# Sheet1.net
KiCad netlist of a schematic drawn in Altium Designer
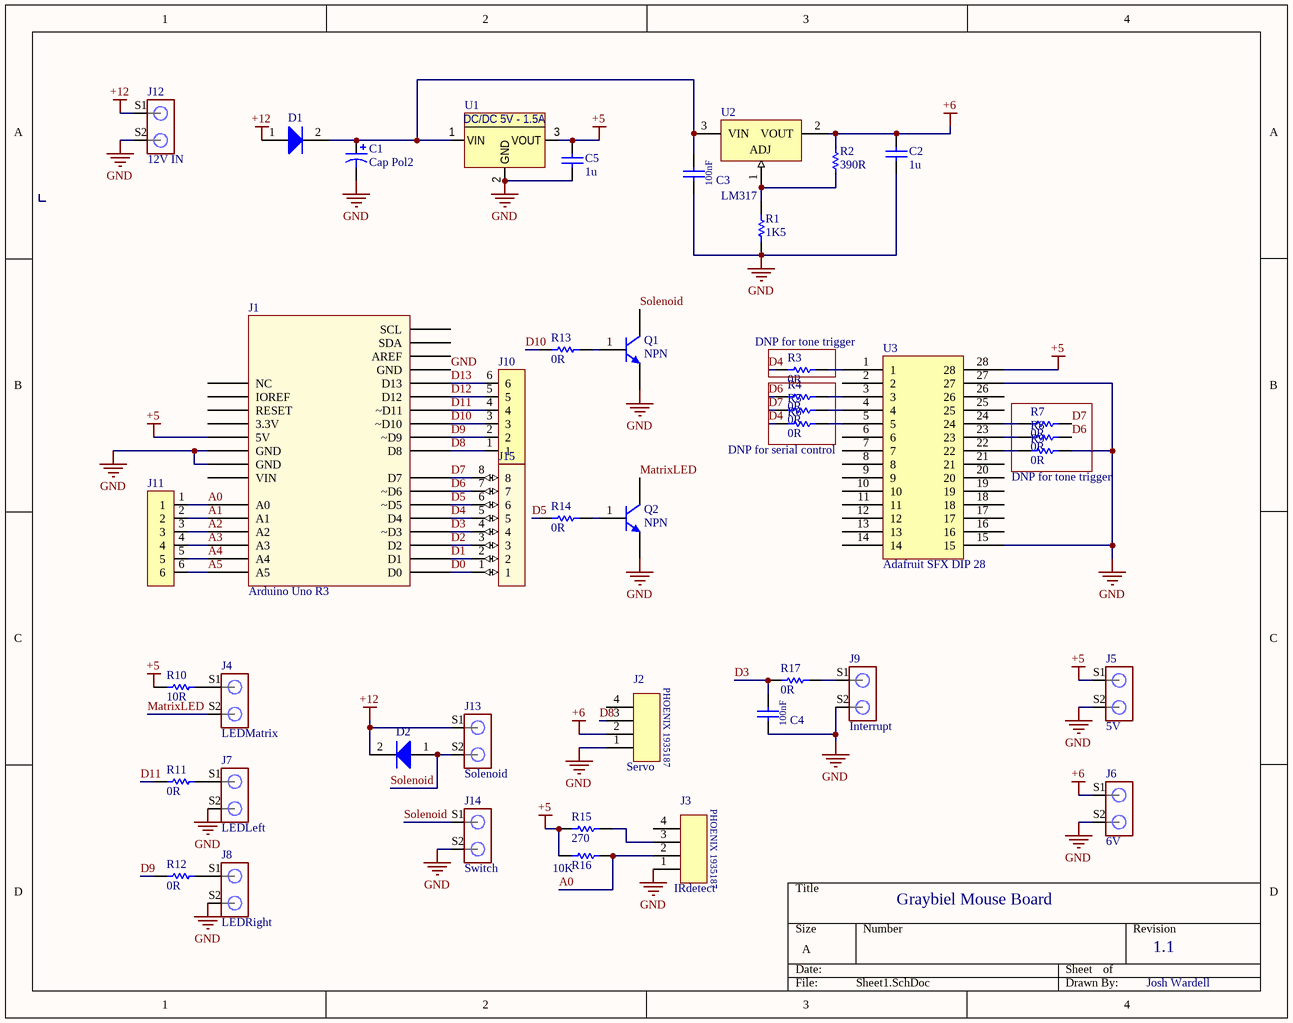
[diagram p0: Sheet1.SchDoc]

(export (version "E")
  (design (tool "Eeschema 10.0.6"))
  (components
    (comp (ref "C1")
      (value "Cap Pol2")
      (footprint "PCB-xqaiwfy5uu00k2ym2klb-1")
      (description "Capacitor; Alum Electrolytic; Cap 100 uF; Tol 20%; Vol-Rtg 25 VDC; Radial; 8x11.5; Bulk")
      (fields (field (name "MANUFACTURER PART NUMBER") "ECE-A1EN101U"))
      (libsource (lib "CommunityVault") (part "SYM-07bcccec45f2d87b-1"))
    )
    (comp (ref "C2")
      (value "1u")
      (footprint "CAPC2013X135X45ML10T25")
      (description "CAP CER 1UF 16V 10% X7R 0805")
      (libsource (lib "CommunityVault") (part "CAP-2"))
    )
    (comp (ref "C3")
      (value "SYM-3c98f6df3913e35f-6")
      (footprint "PCB-ukzk5524dky3o1p8ks6j-1")
      (description "Capacitor; Ceramic; Cap 0.1 uF; Tol 10%; Vol-Rtg 50 VDC; SMT; 0805; X7R; Cut Tape")
      (fields (field (name "MANUFACTURER PART NUMBER") "08055C104KAT2A"))
      (libsource (lib "CommunityVault") (part "SYM-3c98f6df3913e35f-6"))
    )
    (comp (ref "C4")
      (value "SYM-3c98f6df3913e35f-6")
      (footprint "PCB-ukzk5524dky3o1p8ks6j-1")
      (description "Capacitor; Ceramic; Cap 0.1 uF; Tol 10%; Vol-Rtg 50 VDC; SMT; 0805; X7R; Cut Tape")
      (fields (field (name "MANUFACTURER PART NUMBER") "08055C104KAT2A"))
      (libsource (lib "CommunityVault") (part "CMP-3c98f6df3913e35f-15"))
    )
    (comp (ref "C5")
      (value "1u")
      (footprint "CAPC2013X135X45ML10T25")
      (description "CAP CER 1UF 16V 10% X7R 0805")
      (libsource (lib "CommunityVault") (part "CAP-2"))
    )
    (comp (ref "D1")
      (value "SYM-5df394efdd628234-1")
      (footprint "PCB-b6kvxtdabtic7bh9bv58-1")
      (description "Rectifier diode [Diotec] 1N4004 Rectifier diode")
      (libsource (lib "CommunityVault") (part "CMP-5df394efdd628234-2"))
    )
    (comp (ref "D2")
      (value "SYM-5df394efdd628234-1")
      (footprint "PCB-b6kvxtdabtic7bh9bv58-1")
      (description "Rectifier diode [Diotec] 1N4004 Rectifier diode")
      (libsource (lib "CommunityVault") (part "CMP-5df394efdd628234-2"))
    )
    (comp (ref "J1")
      (value "Arduino Uno R3")
      (footprint "PCB-5e3n8s0ey5jqr2f9nncc-1")
      (description "Microcontroller board, Uno [Arduino] A000066 Microcontroller board, Uno 7640152110092")
      (fields (field (name "MANUFACTURER PART NUMBER") "A000066"))
      (libsource (lib "CommunityVault") (part "CMP-1073962-46"))
    )
    (comp (ref "J2")
      (value "Servo")
      (footprint "PCB-v9l72avc46uddy7fpuqf-1")
      (description "Screw terminal 2.50 mm² Number of pins 4 PT 1, 5/ 4-5, 0-H Phoenix Contact Green 1 pc(s)")
      (libsource (lib "CommunityVault") (part "CMP-f0b139bb75412f76-5"))
    )
    (comp (ref "J3")
      (value "IRdetect")
      (footprint "PCB-v9l72avc46uddy7fpuqf-1")
      (description "Screw terminal 2.50 mm² Number of pins 4 PT 1, 5/ 4-5, 0-H Phoenix Contact Green 1 pc(s)")
      (libsource (lib "CommunityVault") (part "CMP-f0b139bb75412f76-5"))
    )
    (comp (ref "J4")
      (value "LEDMatrix")
      (footprint "PCB-723450-1")
      (description "TERM BLOCK HEADER 2POS 5MM BLACK")
      (libsource (lib "CommunityVault") (part "CMP-723450-4"))
    )
    (comp (ref "J5")
      (value "5V")
      (footprint "PCB-723450-1")
      (description "TERM BLOCK HEADER 2POS 5MM BLACK")
      (libsource (lib "CommunityVault") (part "CMP-723450-4"))
    )
    (comp (ref "J6")
      (value "6V")
      (footprint "PCB-723450-1")
      (description "TERM BLOCK HEADER 2POS 5MM BLACK")
      (libsource (lib "CommunityVault") (part "CMP-723450-4"))
    )
    (comp (ref "J7")
      (value "LEDLeft")
      (footprint "PCB-723450-1")
      (description "TERM BLOCK HEADER 2POS 5MM BLACK")
      (libsource (lib "CommunityVault") (part "SYM-723450-1"))
    )
    (comp (ref "J8")
      (value "LEDRight")
      (footprint "PCB-723450-1")
      (description "TERM BLOCK HEADER 2POS 5MM BLACK")
      (libsource (lib "CommunityVault") (part "SYM-723450-1"))
    )
    (comp (ref "J9")
      (value "Interrupt")
      (footprint "PCB-723450-1")
      (description "TERM BLOCK HEADER 2POS 5MM BLACK")
      (libsource (lib "CommunityVault") (part "SYM-723450-1"))
    )
    (comp (ref "J10")
      (value "TE Connectivity / AMP 3-644456-5")
      (footprint "PCB-oudem42uhcimrbfznktg-1")
      (description "MTA-100 Series 6 Position 2.54 mm Pitch Single Row Tin Plated Header")
      (libsource (lib "CommunityVault") (part "CMP-7ab1b1e1ad8ca576-9"))
    )
    (comp (ref "J11")
      (value "TE Connectivity / AMP 3-644456-5")
      (footprint "PCB-oudem42uhcimrbfznktg-1")
      (description "MTA-100 Series 6 Position 2.54 mm Pitch Single Row Tin Plated Header")
      (libsource (lib "") (part "CMP-7ab1b1e1ad8ca576-9_1"))
    )
    (comp (ref "J12")
      (value "12V IN")
      (footprint "PCB-723450-1")
      (description "TERM BLOCK HEADER 2POS 5MM BLACK")
      (libsource (lib "CommunityVault") (part "CMP-723450-4"))
    )
    (comp (ref "J13")
      (value "Solenoid")
      (footprint "PCB-723450-1")
      (description "TERM BLOCK HEADER 2POS 5MM BLACK")
      (libsource (lib "CommunityVault") (part "SYM-723450-1"))
    )
    (comp (ref "J14")
      (value "Switch")
      (footprint "PCB-723450-1")
      (description "TERM BLOCK HEADER 2POS 5MM BLACK")
      (libsource (lib "CommunityVault") (part "SYM-723450-1"))
    )
    (comp (ref "J15")
      (value "Samtec TSW-108-07-L-S")
      (footprint "PCB-o70tqi8axh3k6d5wp5n8-1")
      (description "HEADER, 2.54MM, THT VERT, 8POS; Series: TSW; Pitch Spacing: 2.54mm; No. of Rows: 1;")
      (fields (field (name "MANUFACTURER PART NUMBER") "TSW-108-07-L-S"))
      (libsource (lib "CommunityVault") (part "CMP-69fea0f06b37b639-1"))
    )
    (comp (ref "Q1")
      (value "NPN")
      (footprint "PCB-7rwmerlkdpdu5vtj8obn-1")
      (description "Trans Darlington NPN 60V 5A 2000mW Automotive 3-Pin(3+Tab) TO-220AB Bag")
      (fields (field (name "MANUFACTURER PART NUMBER") "TIP120"))
      (libsource (lib "CommunityVault") (part "CMP-3d84f48b638ce243-2"))
    )
    (comp (ref "Q2")
      (value "NPN")
      (footprint "PCB-7rwmerlkdpdu5vtj8obn-1")
      (description "Trans Darlington NPN 60V 5A 2000mW Automotive 3-Pin(3+Tab) TO-220AB Bag")
      (fields (field (name "MANUFACTURER PART NUMBER") "TIP120"))
      (libsource (lib "CommunityVault") (part "CMP-3d84f48b638ce243-2"))
    )
    (comp (ref "R1")
      (value "Res1")
      (footprint "PCB-lpea0est4zq6qerl2uei-1")
      (fields (field (name "RESISTANCE") "1K5") (field (name "MANUFACTURER PART NUMBER") "ERJ-6ENF3900V"))
      (libsource (lib "CommunityVault") (part "CMP-7c05b642f7a2a3c2-1"))
    )
    (comp (ref "R2")
      (value "Panasonic ERJ-6ENF1501V")
      (footprint "RESC2013X70X40ML20T20")
      (description "Thick Film Resistors 0805 1.5Kohms 1% Tol")
      (fields (field (name "RESISTANCE") "390R"))
      (libsource (lib "CommunityVault") (part "CMP-3652227-3"))
    )
    (comp (ref "R3")
      (value "0R")
      (footprint "RESC2013X65X35NL10T20")
      (description "Panasonic Resistor 0 Ohm 0805")
      (fields
        (field (name "MANUFACTURER PART NUMBER") "ERJ-6GEY0R00V")
        (field (name "MANUFACTURER") "Panasonic")
      )
      (libsource (lib "CommunityVault") (part "RES-2"))
    )
    (comp (ref "R4")
      (value "0R")
      (footprint "RESC2013X65X35NL10T20")
      (description "Panasonic Resistor 0 Ohm 0805")
      (fields
        (field (name "MANUFACTURER PART NUMBER") "ERJ-6GEY0R00V")
        (field (name "MANUFACTURER") "Panasonic")
      )
      (libsource (lib "CommunityVault") (part "RES-2"))
    )
    (comp (ref "R5")
      (value "0R")
      (footprint "RESC2013X65X35NL10T20")
      (description "Panasonic Resistor 0 Ohm 0805")
      (fields
        (field (name "MANUFACTURER PART NUMBER") "ERJ-6GEY0R00V")
        (field (name "MANUFACTURER") "Panasonic")
      )
      (libsource (lib "CommunityVault") (part "RES-2"))
    )
    (comp (ref "R6")
      (value "0R")
      (footprint "RESC2013X65X35NL10T20")
      (description "Panasonic Resistor 0 Ohm 0805")
      (fields
        (field (name "MANUFACTURER PART NUMBER") "ERJ-6GEY0R00V")
        (field (name "MANUFACTURER") "Panasonic")
      )
      (libsource (lib "CommunityVault") (part "RES-2"))
    )
    (comp (ref "R7")
      (value "0R")
      (footprint "RESC2013X65X35NL10T20")
      (description "Panasonic Resistor 0 Ohm 0805")
      (fields
        (field (name "MANUFACTURER PART NUMBER") "ERJ-6GEY0R00V")
        (field (name "MANUFACTURER") "Panasonic")
      )
      (libsource (lib "CommunityVault") (part "RES-2"))
    )
    (comp (ref "R8")
      (value "0R")
      (footprint "RESC2013X65X35NL10T20")
      (description "Panasonic Resistor 0 Ohm 0805")
      (fields
        (field (name "MANUFACTURER PART NUMBER") "ERJ-6GEY0R00V")
        (field (name "MANUFACTURER") "Panasonic")
      )
      (libsource (lib "CommunityVault") (part "RES-2"))
    )
    (comp (ref "R9")
      (value "0R")
      (footprint "RESC2013X65X35NL10T20")
      (description "Panasonic Resistor 0 Ohm 0805")
      (fields
        (field (name "MANUFACTURER PART NUMBER") "ERJ-6GEY0R00V")
        (field (name "MANUFACTURER") "Panasonic")
      )
      (libsource (lib "CommunityVault") (part "RES-2"))
    )
    (comp (ref "R10")
      (value "10R")
      (footprint "PCB-tug24or67yk1neb49pkx-1")
      (description "Surface Mount Chip Resistor, Thick Film, CRS Series, 10 ohm, 1 W, 5%, 400 V, 2010 [5025 Metric]")
      (fields (field (name "MANUFACTURER PART NUMBER") "CRS2010-JX-100ELF"))
      (libsource (lib "CommunityVault") (part "CMP-196dd32a6f1ac6aa-1"))
    )
    (comp (ref "R11")
      (value "0R")
      (footprint "RESC2013X65X35NL10T20")
      (description "Panasonic Resistor 0 Ohm 0805")
      (fields
        (field (name "MANUFACTURER PART NUMBER") "ERJ-6GEY0R00V")
        (field (name "MANUFACTURER") "Panasonic")
      )
      (libsource (lib "CommunityVault") (part "RES-2"))
    )
    (comp (ref "R12")
      (value "0R")
      (footprint "RESC2013X65X35NL10T20")
      (description "Panasonic Resistor 0 Ohm 0805")
      (fields
        (field (name "MANUFACTURER PART NUMBER") "ERJ-6GEY0R00V")
        (field (name "MANUFACTURER") "Panasonic")
      )
      (libsource (lib "CommunityVault") (part "RES-2"))
    )
    (comp (ref "R13")
      (value "0R")
      (footprint "RESC2013X65X35NL10T20")
      (description "Panasonic Resistor 0 Ohm 0805")
      (fields
        (field (name "MANUFACTURER PART NUMBER") "ERJ-6GEY0R00V")
        (field (name "MANUFACTURER") "Panasonic")
      )
      (libsource (lib "CommunityVault") (part "RES-2"))
    )
    (comp (ref "R14")
      (value "0R")
      (footprint "RESC2013X65X35NL10T20")
      (description "Panasonic Resistor 0 Ohm 0805")
      (fields
        (field (name "MANUFACTURER PART NUMBER") "ERJ-6GEY0R00V")
        (field (name "MANUFACTURER") "Panasonic")
      )
      (libsource (lib "CommunityVault") (part "RES-2"))
    )
    (comp (ref "R15")
      (value "270")
      (footprint "RESC2013X50X30ML20T20")
      (description "Thick film resistor")
      (libsource (lib "CommunityVault") (part "RES-2"))
    )
    (comp (ref "R16")
      (value "10K")
      (footprint "PCB-jmrvwrcl0dwqv7ke6mfz-1")
      (description "Res Thick Film 0805 10K Ohm 1% 0.125W(1/8W) ±100ppm/C Molded SMD Automotive Paper T/R")
      (libsource (lib "CommunityVault") (part "CMP-4716692-8"))
    )
    (comp (ref "R17")
      (value "0R")
      (footprint "RESC2013X65X35NL10T20")
      (description "Panasonic Resistor 0 Ohm 0805")
      (fields
        (field (name "MANUFACTURER PART NUMBER") "ERJ-6GEY0R00V")
        (field (name "MANUFACTURER") "Panasonic")
      )
      (libsource (lib "CommunityVault") (part "RES-2"))
    )
    (comp (ref "U1")
      (value "Murata OKI-78SR-5/1.5-W36H-C")
      (footprint "OKI-78SR-5/1.5-W36H-C")
      (description "DC/DC Converters 7.5W 24V 5Vout 1.5A Horizontal Mount")
      (libsource (lib "CommunityVault") (part "CMP-3191555-6"))
    )
    (comp (ref "U2")
      (value "LM317")
      (footprint "PCB-d58nmo5dooqatgqjfgwp-1")
      (libsource (lib "CommunityVault") (part "CMP-bbed72e7deae642a-4"))
    )
    (comp (ref "U3")
      (value "Adafruit SFX DIP 28")
      (footprint "PCB-bcfalq7aliu97ymsl87v-1")
      (description "Adafruit Audio FX Sound Board - WAV/OGG Trigger with 2MB Flash")
      (fields (field (name "MANUFACTURER") "Adafruit") (field (name "MANUFACTURER PART NUMBER") "2133"))
      (libsource (lib "CommunityVault") (part "CMP-4t4546zhglsm7c6ybtqr-1"))
    )
  )
  (nets
    (net (code "1") (name "+5") (class "Default")
      (node (ref "C5") (pin "2") (pinfunction "2_2") (pintype "passive"))
      (node (ref "J1") (pin "5V") (pinfunction "5V_5V") (pintype "passive"))
      (node (ref "J5") (pin "S1") (pinfunction "S1_S1") (pintype "passive"))
      (node (ref "R10") (pin "2") (pinfunction "2_2") (pintype "passive"))
      (node (ref "R15") (pin "1") (pinfunction "1_1") (pintype "passive"))
      (node (ref "R16") (pin "1") (pinfunction "1_1") (pintype "passive"))
      (node (ref "U1") (pin "3") (pinfunction "VOUT_3") (pintype "power_in"))
      (node (ref "U3") (pin "28") (pinfunction "28_28") (pintype "passive"))
    )
    (net (code "2") (name "+6") (class "Default")
      (node (ref "C2") (pin "2") (pinfunction "2_2") (pintype "passive"))
      (node (ref "J2") (pin "2") (pinfunction "2_2") (pintype "passive"))
      (node (ref "J6") (pin "S1") (pinfunction "S1_S1") (pintype "passive"))
      (node (ref "R2") (pin "2") (pinfunction "2_2") (pintype "passive"))
      (node (ref "U2") (pin "2") (pinfunction "VOUT_2") (pintype "power_in"))
    )
    (net (code "3") (name "+12") (class "Default")
      (node (ref "D1") (pin "1") (pinfunction "+_1") (pintype "passive"))
      (node (ref "D2") (pin "2") (pinfunction "-_2") (pintype "passive"))
      (node (ref "J12") (pin "S1") (pinfunction "S1_S1") (pintype "passive"))
      (node (ref "J13") (pin "S1") (pinfunction "S1_S1") (pintype "passive"))
    )
    (net (code "4") (name "/A0") (class "Default")
      (node (ref "J1") (pin "A0") (pinfunction "A0_A0") (pintype "passive"))
      (node (ref "J11") (pin "1") (pinfunction "1_1") (pintype "passive"))
      (node (ref "J3") (pin "2") (pinfunction "2_2") (pintype "passive"))
      (node (ref "R16") (pin "2") (pinfunction "2_2") (pintype "passive"))
    )
    (net (code "5") (name "/A1") (class "Default")
      (node (ref "J1") (pin "A1") (pinfunction "A1_A1") (pintype "passive"))
      (node (ref "J11") (pin "2") (pinfunction "2_2") (pintype "passive"))
    )
    (net (code "6") (name "/A2") (class "Default")
      (node (ref "J1") (pin "A2") (pinfunction "A2_A2") (pintype "passive"))
      (node (ref "J11") (pin "3") (pinfunction "3_3") (pintype "passive"))
    )
    (net (code "7") (name "/A3") (class "Default")
      (node (ref "J1") (pin "A3") (pinfunction "A3_A3") (pintype "passive"))
      (node (ref "J11") (pin "4") (pinfunction "4_4") (pintype "passive"))
    )
    (net (code "8") (name "/A4") (class "Default")
      (node (ref "J1") (pin "A4") (pinfunction "A4_A4") (pintype "passive"))
      (node (ref "J11") (pin "5") (pinfunction "5_5") (pintype "passive"))
    )
    (net (code "9") (name "/A5") (class "Default")
      (node (ref "J1") (pin "A5") (pinfunction "A5_A5") (pintype "passive"))
      (node (ref "J11") (pin "6") (pinfunction "6_6") (pintype "passive"))
    )
    (net (code "10") (name "/D0") (class "Default")
      (node (ref "J1") (pin "D0") (pinfunction "D0_D0") (pintype "passive"))
      (node (ref "J15") (pin "1") (pinfunction "1_1") (pintype "bidirectional"))
    )
    (net (code "11") (name "/D1") (class "Default")
      (node (ref "J1") (pin "D1") (pinfunction "D1_D1") (pintype "passive"))
      (node (ref "J15") (pin "2") (pinfunction "2_2") (pintype "bidirectional"))
    )
    (net (code "12") (name "/D2") (class "Default")
      (node (ref "J1") (pin "D2") (pinfunction "D2_D2") (pintype "passive"))
      (node (ref "J15") (pin "3") (pinfunction "3_3") (pintype "bidirectional"))
    )
    (net (code "13") (name "/D3") (class "Default")
      (node (ref "C4") (pin "2") (pinfunction "2_2") (pintype "passive"))
      (node (ref "J1") (pin "D3") (pinfunction "~D3_D3") (pintype "passive"))
      (node (ref "J15") (pin "4") (pinfunction "4_4") (pintype "bidirectional"))
      (node (ref "R17") (pin "1") (pinfunction "1_1") (pintype "passive"))
    )
    (net (code "14") (name "/D4") (class "Default")
      (node (ref "J1") (pin "D4") (pinfunction "D4_D4") (pintype "passive"))
      (node (ref "J15") (pin "5") (pinfunction "5_5") (pintype "bidirectional"))
      (node (ref "R3") (pin "1") (pinfunction "1_1") (pintype "passive"))
      (node (ref "R6") (pin "1") (pinfunction "1_1") (pintype "passive"))
    )
    (net (code "15") (name "/D5") (class "Default")
      (node (ref "J1") (pin "D5") (pinfunction "~D5_D5") (pintype "passive"))
      (node (ref "J15") (pin "6") (pinfunction "6_6") (pintype "bidirectional"))
      (node (ref "R14") (pin "1") (pinfunction "1_1") (pintype "passive"))
    )
    (net (code "16") (name "/D6") (class "Default")
      (node (ref "J1") (pin "D6") (pinfunction "~D6_D6") (pintype "passive"))
      (node (ref "J15") (pin "7") (pinfunction "7_7") (pintype "bidirectional"))
      (node (ref "R4") (pin "1") (pinfunction "1_1") (pintype "passive"))
      (node (ref "R8") (pin "2") (pinfunction "2_2") (pintype "passive"))
    )
    (net (code "17") (name "/D7") (class "Default")
      (node (ref "J1") (pin "D7") (pinfunction "D7_D7") (pintype "passive"))
      (node (ref "J15") (pin "8") (pinfunction "8_8") (pintype "bidirectional"))
      (node (ref "R5") (pin "1") (pinfunction "1_1") (pintype "passive"))
      (node (ref "R7") (pin "2") (pinfunction "2_2") (pintype "passive"))
    )
    (net (code "18") (name "/D8") (class "Default")
      (node (ref "J1") (pin "D8") (pinfunction "D8_D8") (pintype "passive"))
      (node (ref "J10") (pin "1") (pinfunction "1_1") (pintype "passive"))
      (node (ref "J2") (pin "3") (pinfunction "3_3") (pintype "passive"))
    )
    (net (code "19") (name "/D9") (class "Default")
      (node (ref "J1") (pin "D9") (pinfunction "~D9_D9") (pintype "passive"))
      (node (ref "J10") (pin "2") (pinfunction "2_2") (pintype "passive"))
      (node (ref "R12") (pin "1") (pinfunction "1_1") (pintype "passive"))
    )
    (net (code "20") (name "/D10") (class "Default")
      (node (ref "J1") (pin "D10") (pinfunction "~D10_D10") (pintype "passive"))
      (node (ref "J10") (pin "3") (pinfunction "3_3") (pintype "passive"))
      (node (ref "R13") (pin "1") (pinfunction "1_1") (pintype "passive"))
    )
    (net (code "21") (name "/D11") (class "Default")
      (node (ref "J1") (pin "D11") (pinfunction "~D11_D11") (pintype "passive"))
      (node (ref "J10") (pin "4") (pinfunction "4_4") (pintype "passive"))
      (node (ref "R11") (pin "1") (pinfunction "1_1") (pintype "passive"))
    )
    (net (code "22") (name "/D12") (class "Default")
      (node (ref "J1") (pin "D12") (pinfunction "D12_D12") (pintype "passive"))
      (node (ref "J10") (pin "5") (pinfunction "5_5") (pintype "passive"))
    )
    (net (code "23") (name "/D13") (class "Default")
      (node (ref "J1") (pin "D13") (pinfunction "D13_D13") (pintype "passive"))
      (node (ref "J10") (pin "6") (pinfunction "6_6") (pintype "passive"))
    )
    (net (code "24") (name "/MatrixLED") (class "Default")
      (node (ref "J4") (pin "S2") (pinfunction "S2_S2") (pintype "passive"))
      (node (ref "Q2") (pin "2") (pinfunction "C_2") (pintype "passive"))
    )
    (net (code "25") (name "/Solenoid") (class "Default")
      (node (ref "D2") (pin "1") (pinfunction "+_1") (pintype "passive"))
      (node (ref "J13") (pin "S2") (pinfunction "S2_S2") (pintype "passive"))
      (node (ref "J14") (pin "S1") (pinfunction "S1_S1") (pintype "passive"))
      (node (ref "Q1") (pin "2") (pinfunction "C_2") (pintype "passive"))
    )
    (net (code "26") (name "GND") (class "Default")
      (node (ref "C1") (pin "2") (pinfunction "2_2") (pintype "passive"))
      (node (ref "C2") (pin "1") (pinfunction "1_1") (pintype "passive"))
      (node (ref "C3") (pin "1") (pinfunction "1_1") (pintype "passive"))
      (node (ref "C4") (pin "1") (pinfunction "1_1") (pintype "passive"))
      (node (ref "C5") (pin "1") (pinfunction "1_1") (pintype "passive"))
      (node (ref "J1") (pin "GND1") (pinfunction "GND_GND1") (pintype "passive"))
      (node (ref "J1") (pin "GND2") (pinfunction "GND_GND2") (pintype "passive"))
      (node (ref "J1") (pin "GND3") (pinfunction "GND_GND3") (pintype "passive"))
      (node (ref "J12") (pin "S2") (pinfunction "S2_S2") (pintype "passive"))
      (node (ref "J14") (pin "S2") (pinfunction "S2_S2") (pintype "passive"))
      (node (ref "J2") (pin "1") (pinfunction "1_1") (pintype "passive"))
      (node (ref "J3") (pin "1") (pinfunction "1_1") (pintype "passive"))
      (node (ref "J5") (pin "S2") (pinfunction "S2_S2") (pintype "passive"))
      (node (ref "J6") (pin "S2") (pinfunction "S2_S2") (pintype "passive"))
      (node (ref "J7") (pin "S2") (pinfunction "S2_S2") (pintype "passive"))
      (node (ref "J8") (pin "S2") (pinfunction "S2_S2") (pintype "passive"))
      (node (ref "J9") (pin "S2") (pinfunction "S2_S2") (pintype "passive"))
      (node (ref "Q1") (pin "3") (pinfunction "E_3") (pintype "passive"))
      (node (ref "Q2") (pin "3") (pinfunction "E_3") (pintype "passive"))
      (node (ref "R1") (pin "1") (pinfunction "1_1") (pintype "passive"))
      (node (ref "R9") (pin "2") (pinfunction "2_2") (pintype "passive"))
      (node (ref "U1") (pin "2") (pinfunction "GND_2") (pintype "passive"))
      (node (ref "U3") (pin "15") (pinfunction "15_15") (pintype "passive"))
      (node (ref "U3") (pin "27") (pinfunction "27_27") (pintype "passive"))
    )
    (net (code "27") (name "Net-(D1--)") (class "Default")
      (node (ref "C1") (pin "1") (pinfunction "1_1") (pintype "passive"))
      (node (ref "C3") (pin "2") (pinfunction "2_2") (pintype "passive"))
      (node (ref "D1") (pin "2") (pinfunction "-_2") (pintype "passive"))
      (node (ref "U1") (pin "1") (pinfunction "VIN_1") (pintype "power_in"))
      (node (ref "U2") (pin "3") (pinfunction "VIN_3") (pintype "power_in"))
    )
    (net (code "28") (name "Net-(J3-Pad3)") (class "Default")
      (node (ref "J3") (pin "3") (pinfunction "3_3") (pintype "passive"))
      (node (ref "R15") (pin "2") (pinfunction "2_2") (pintype "passive"))
    )
    (net (code "29") (name "Net-(J4-PadS1)") (class "Default")
      (node (ref "J4") (pin "S1") (pinfunction "S1_S1") (pintype "passive"))
      (node (ref "R10") (pin "1") (pinfunction "1_1") (pintype "passive"))
    )
    (net (code "30") (name "Net-(J7-PadS1)") (class "Default")
      (node (ref "J7") (pin "S1") (pinfunction "S1_S1") (pintype "passive"))
      (node (ref "R11") (pin "2") (pinfunction "2_2") (pintype "passive"))
    )
    (net (code "31") (name "Net-(J8-PadS1)") (class "Default")
      (node (ref "J8") (pin "S1") (pinfunction "S1_S1") (pintype "passive"))
      (node (ref "R12") (pin "2") (pinfunction "2_2") (pintype "passive"))
    )
    (net (code "32") (name "Net-(J9-PadS1)") (class "Default")
      (node (ref "J9") (pin "S1") (pinfunction "S1_S1") (pintype "passive"))
      (node (ref "R17") (pin "2") (pinfunction "2_2") (pintype "passive"))
    )
    (net (code "33") (name "Net-(Q1-B)") (class "Default")
      (node (ref "Q1") (pin "1") (pinfunction "B_1") (pintype "passive"))
      (node (ref "R13") (pin "2") (pinfunction "2_2") (pintype "passive"))
    )
    (net (code "34") (name "Net-(Q2-B)") (class "Default")
      (node (ref "Q2") (pin "1") (pinfunction "B_1") (pintype "passive"))
      (node (ref "R14") (pin "2") (pinfunction "2_2") (pintype "passive"))
    )
    (net (code "35") (name "Net-(R3-Pad2)") (class "Default")
      (node (ref "R3") (pin "2") (pinfunction "2_2") (pintype "passive"))
      (node (ref "U3") (pin "1") (pinfunction "1_1") (pintype "passive"))
    )
    (net (code "36") (name "Net-(R4-Pad2)") (class "Default")
      (node (ref "R4") (pin "2") (pinfunction "2_2") (pintype "passive"))
      (node (ref "U3") (pin "3") (pinfunction "3_3") (pintype "passive"))
    )
    (net (code "37") (name "Net-(R5-Pad2)") (class "Default")
      (node (ref "R5") (pin "2") (pinfunction "2_2") (pintype "passive"))
      (node (ref "U3") (pin "4") (pinfunction "4_4") (pintype "passive"))
    )
    (net (code "38") (name "Net-(R6-Pad2)") (class "Default")
      (node (ref "R6") (pin "2") (pinfunction "2_2") (pintype "passive"))
      (node (ref "U3") (pin "5") (pinfunction "5_5") (pintype "passive"))
    )
    (net (code "39") (name "Net-(R7-Pad1)") (class "Default")
      (node (ref "R7") (pin "1") (pinfunction "1_1") (pintype "passive"))
      (node (ref "U3") (pin "24") (pinfunction "24_24") (pintype "passive"))
    )
    (net (code "40") (name "Net-(R8-Pad1)") (class "Default")
      (node (ref "R8") (pin "1") (pinfunction "1_1") (pintype "passive"))
      (node (ref "U3") (pin "23") (pinfunction "23_23") (pintype "passive"))
    )
    (net (code "41") (name "Net-(R9-Pad1)") (class "Default")
      (node (ref "R9") (pin "1") (pinfunction "1_1") (pintype "passive"))
      (node (ref "U3") (pin "22") (pinfunction "22_22") (pintype "passive"))
    )
    (net (code "42") (name "Net-(U2-ADJ)") (class "Default")
      (node (ref "R1") (pin "2") (pinfunction "2_2") (pintype "passive"))
      (node (ref "R2") (pin "1") (pinfunction "1_1") (pintype "passive"))
      (node (ref "U2") (pin "1") (pinfunction "ADJ_1") (pintype "input"))
    )
    (net (code "43") (name "unconnected-(J1-Pad3.3V)") (class "Default")
      (node (ref "J1") (pin "3.3V") (pinfunction "3.3V_3.3V") (pintype "passive"))
    )
    (net (code "44") (name "unconnected-(J1-PadAREF)") (class "Default")
      (node (ref "J1") (pin "AREF") (pinfunction "AREF_AREF") (pintype "passive"))
    )
    (net (code "45") (name "unconnected-(J1-PadIOREF)") (class "Default")
      (node (ref "J1") (pin "IOREF") (pinfunction "IOREF_IOREF") (pintype "passive"))
    )
    (net (code "46") (name "unconnected-(J1-PadNC)") (class "Default")
      (node (ref "J1") (pin "NC") (pinfunction "NC_NC") (pintype "passive"))
    )
    (net (code "47") (name "unconnected-(J1-PadRESET)") (class "Default")
      (node (ref "J1") (pin "RESET") (pinfunction "RESET_RESET") (pintype "passive"))
    )
    (net (code "48") (name "unconnected-(J1-PadSCL)") (class "Default")
      (node (ref "J1") (pin "SCL") (pinfunction "SCL_SCL") (pintype "passive"))
    )
    (net (code "49") (name "unconnected-(J1-PadSDA)") (class "Default")
      (node (ref "J1") (pin "SDA") (pinfunction "SDA_SDA") (pintype "passive"))
    )
    (net (code "50") (name "unconnected-(J1-PadVIN)") (class "Default")
      (node (ref "J1") (pin "VIN") (pinfunction "VIN_VIN") (pintype "passive"))
    )
    (net (code "51") (name "unconnected-(J2-Pad4)") (class "Default")
      (node (ref "J2") (pin "4") (pinfunction "4_4") (pintype "passive"))
    )
    (net (code "52") (name "unconnected-(J3-Pad4)") (class "Default")
      (node (ref "J3") (pin "4") (pinfunction "4_4") (pintype "passive"))
    )
    (net (code "53") (name "unconnected-(U3-Pad2)") (class "Default")
      (node (ref "U3") (pin "2") (pinfunction "2_2") (pintype "passive"))
    )
    (net (code "54") (name "unconnected-(U3-Pad6)") (class "Default")
      (node (ref "U3") (pin "6") (pinfunction "6_6") (pintype "passive"))
    )
    (net (code "55") (name "unconnected-(U3-Pad7)") (class "Default")
      (node (ref "U3") (pin "7") (pinfunction "7_7") (pintype "passive"))
    )
    (net (code "56") (name "unconnected-(U3-Pad8)") (class "Default")
      (node (ref "U3") (pin "8") (pinfunction "8_8") (pintype "passive"))
    )
    (net (code "57") (name "unconnected-(U3-Pad9)") (class "Default")
      (node (ref "U3") (pin "9") (pinfunction "9_9") (pintype "passive"))
    )
    (net (code "58") (name "unconnected-(U3-Pad10)") (class "Default")
      (node (ref "U3") (pin "10") (pinfunction "10_10") (pintype "passive"))
    )
    (net (code "59") (name "unconnected-(U3-Pad11)") (class "Default")
      (node (ref "U3") (pin "11") (pinfunction "11_11") (pintype "passive"))
    )
    (net (code "60") (name "unconnected-(U3-Pad12)") (class "Default")
      (node (ref "U3") (pin "12") (pinfunction "12_12") (pintype "passive"))
    )
    (net (code "61") (name "unconnected-(U3-Pad13)") (class "Default")
      (node (ref "U3") (pin "13") (pinfunction "13_13") (pintype "passive"))
    )
    (net (code "62") (name "unconnected-(U3-Pad14)") (class "Default")
      (node (ref "U3") (pin "14") (pinfunction "14_14") (pintype "passive"))
    )
    (net (code "63") (name "unconnected-(U3-Pad16)") (class "Default")
      (node (ref "U3") (pin "16") (pinfunction "16_16") (pintype "passive"))
    )
    (net (code "64") (name "unconnected-(U3-Pad17)") (class "Default")
      (node (ref "U3") (pin "17") (pinfunction "17_17") (pintype "passive"))
    )
    (net (code "65") (name "unconnected-(U3-Pad18)") (class "Default")
      (node (ref "U3") (pin "18") (pinfunction "18_18") (pintype "passive"))
    )
    (net (code "66") (name "unconnected-(U3-Pad19)") (class "Default")
      (node (ref "U3") (pin "19") (pinfunction "19_19") (pintype "passive"))
    )
    (net (code "67") (name "unconnected-(U3-Pad20)") (class "Default")
      (node (ref "U3") (pin "20") (pinfunction "20_20") (pintype "passive"))
    )
    (net (code "68") (name "unconnected-(U3-Pad21)") (class "Default")
      (node (ref "U3") (pin "21") (pinfunction "21_21") (pintype "passive"))
    )
    (net (code "69") (name "unconnected-(U3-Pad25)") (class "Default")
      (node (ref "U3") (pin "25") (pinfunction "25_25") (pintype "passive"))
    )
    (net (code "70") (name "unconnected-(U3-Pad26)") (class "Default")
      (node (ref "U3") (pin "26") (pinfunction "26_26") (pintype "passive"))
    )
  )
)
